# edition4-mainpart-2.net
KiCad netlist of a schematic drawn in EAGLE
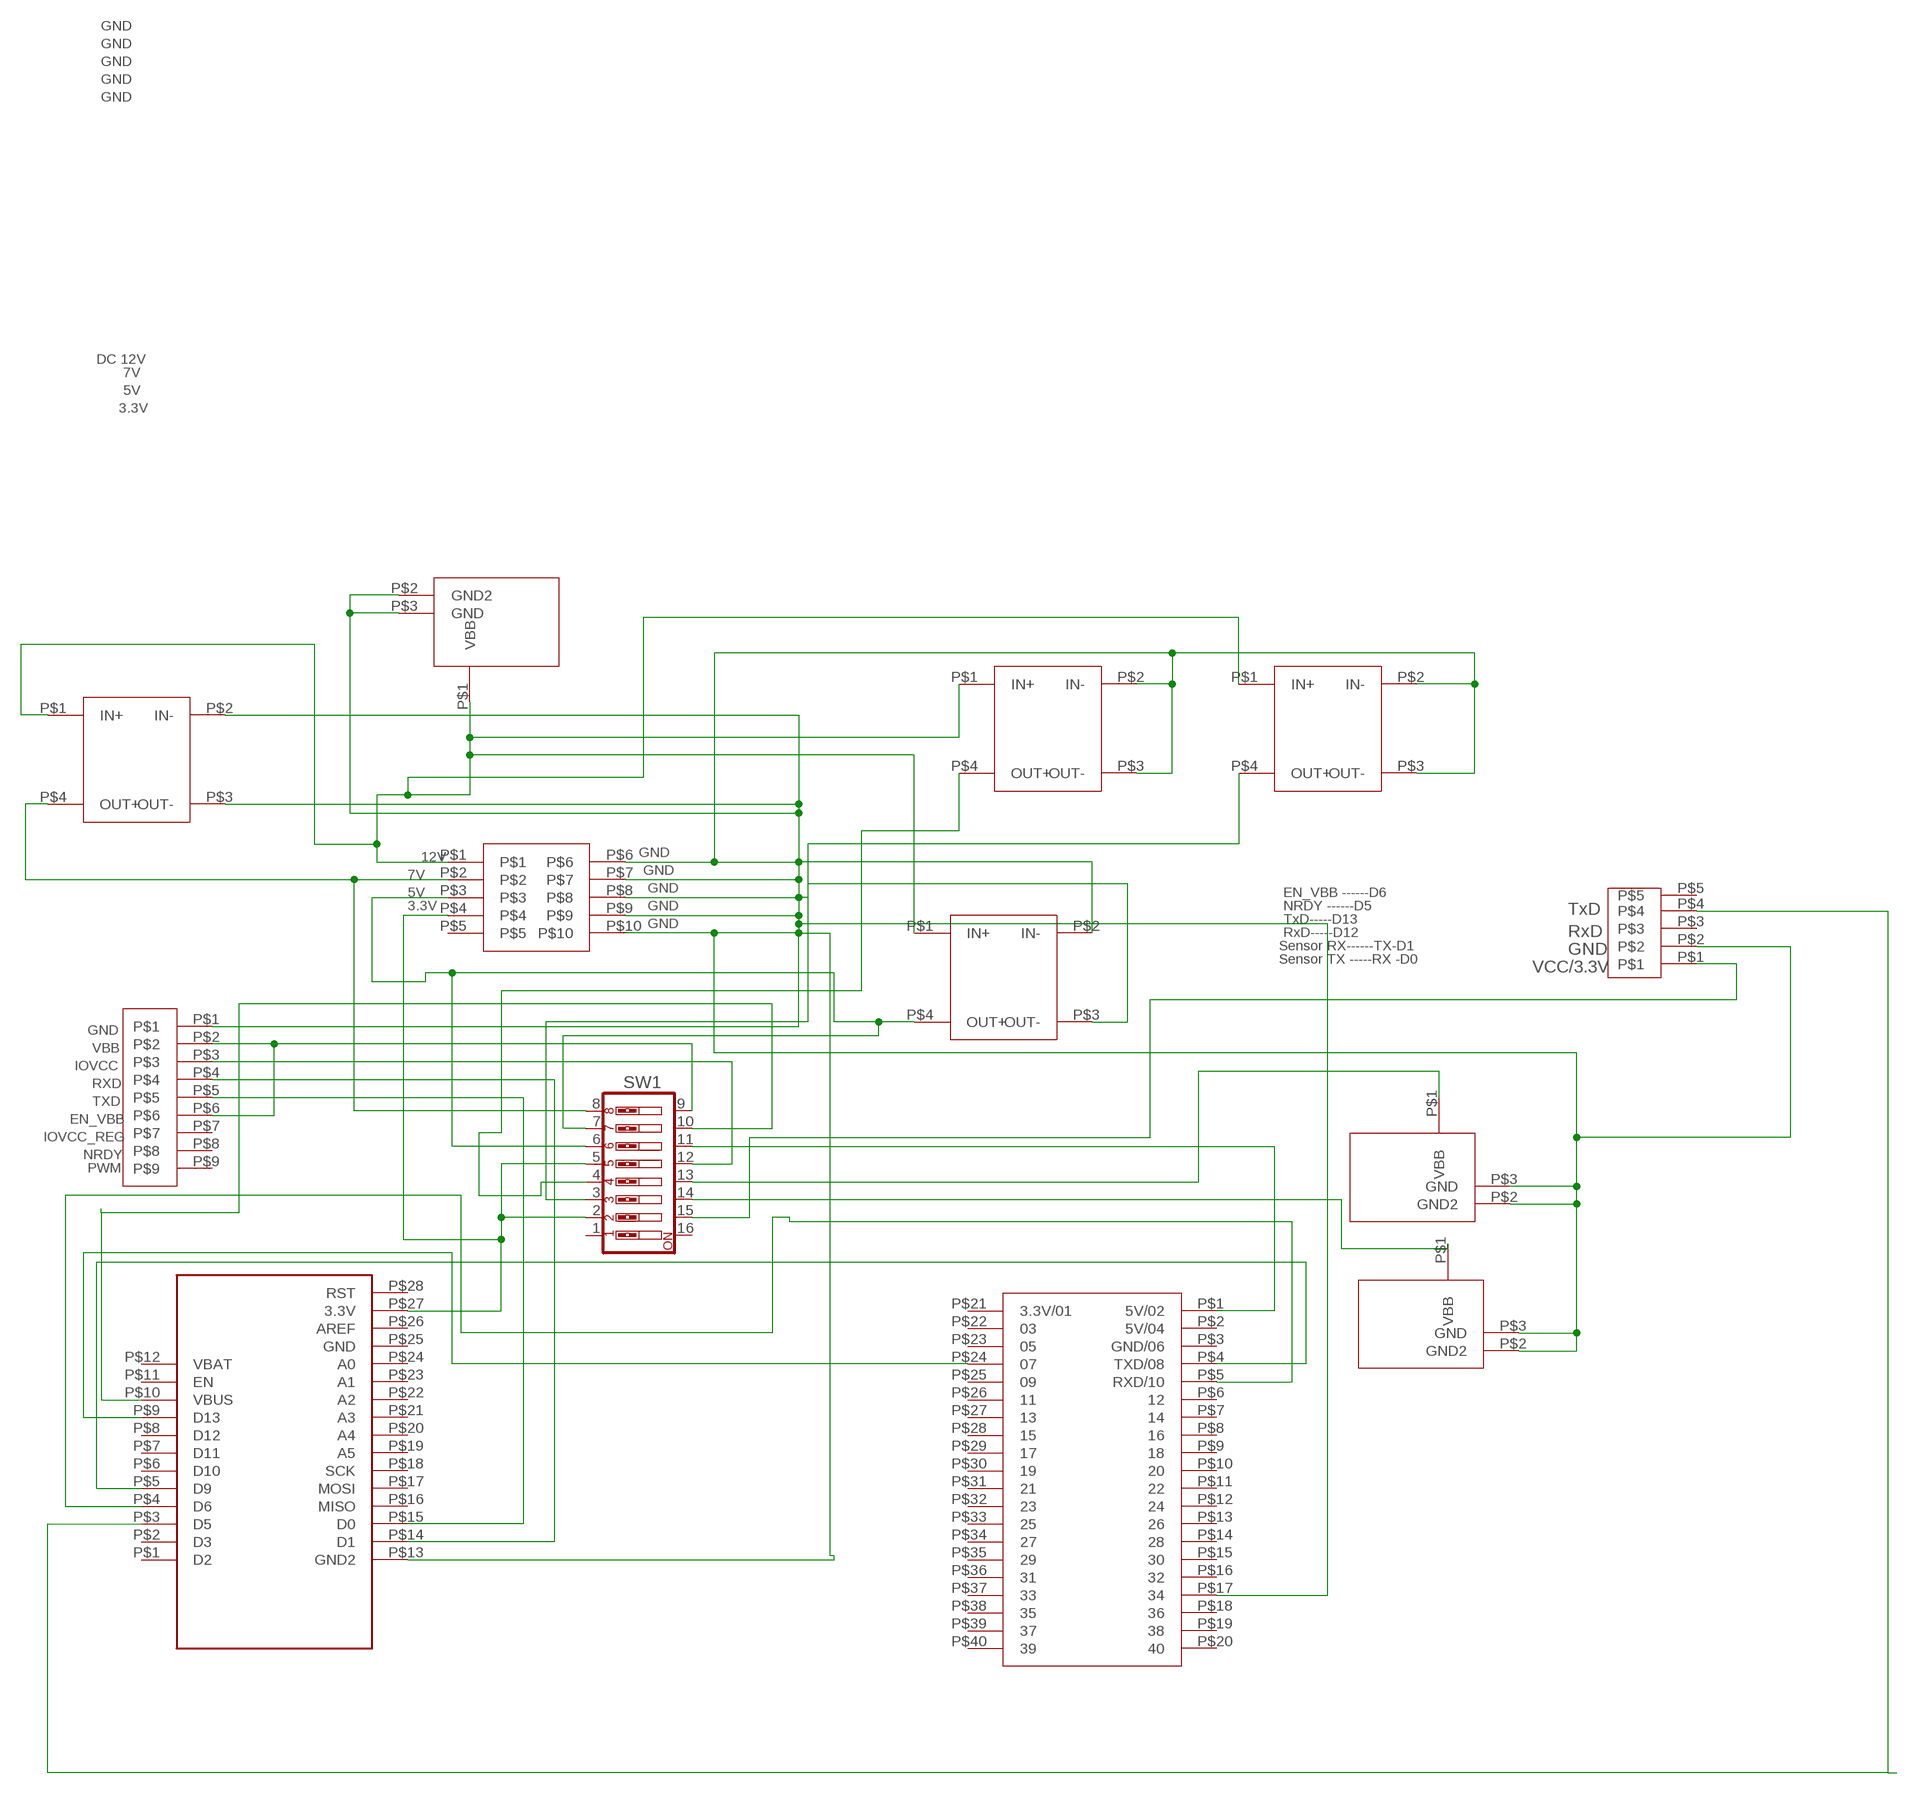
[diagram p0: schematic, sheet 1]

(export (version "E")
  (design (tool "Eeschema 10.0.6"))
  (components
    (comp (ref "SW1")
      (value "SW_DIP-8")
      (footprint "eagle-import:EDG-08")
      (libsource (lib "eagle-import") (part "SW_DIP-8"))
    )
    (comp (ref "U$1")
      (value "MH-MINI-360")
      (footprint "eagle-import:MH-MINI-360")
      (libsource (lib "eagle-import") (part "MH-MINI-360"))
    )
    (comp (ref "U$2")
      (value "MH-MINI-360")
      (footprint "eagle-import:MH-MINI-360")
      (libsource (lib "eagle-import") (part "MH-MINI-360"))
    )
    (comp (ref "U$3")
      (value "POWER")
      (footprint "eagle-import:POWERIN")
      (libsource (lib "eagle-import") (part "POWER"))
    )
    (comp (ref "U$4")
      (value "POWER")
      (footprint "eagle-import:POWERIN")
      (libsource (lib "eagle-import") (part "POWER"))
    )
    (comp (ref "U$5")
      (value "POWER")
      (footprint "eagle-import:POWERIN")
      (libsource (lib "eagle-import") (part "POWER"))
    )
    (comp (ref "U$6")
      (value "MH-MINI-360")
      (footprint "eagle-import:MH-MINI-360")
      (libsource (lib "eagle-import") (part "MH-MINI-360"))
    )
    (comp (ref "U$7")
      (value "MH-MINI-360")
      (footprint "eagle-import:MH-MINI-360")
      (libsource (lib "eagle-import") (part "MH-MINI-360"))
    )
    (comp (ref "U$8")
      (value "PIN")
      (footprint "eagle-import:PIN")
      (libsource (lib "eagle-import") (part "PIN"))
    )
    (comp (ref "U$10")
      (value "FEATHER")
      (footprint "eagle-import:FEATHER")
      (libsource (lib "eagle-import") (part "FEATHER"))
    )
    (comp (ref "U$11")
      (value "RASPBERRYPI")
      (footprint "eagle-import:RASPBERRYPI")
      (libsource (lib "eagle-import") (part "RASPBERRYPI"))
    )
    (comp (ref "U$14")
      (value "2X5FEET")
      (footprint "eagle-import:2X5FEET")
      (libsource (lib "eagle-import") (part "2X5FEET"))
    )
    (comp (ref "U$15")
      (value "9FEETPIN")
      (footprint "eagle-import:9FEETPIN")
      (libsource (lib "eagle-import") (part "9FEETPIN"))
    )
  )
  (nets
    (net (code "1") (name "Net-(SW1-Pad9)") (class "Default")
      (node (ref "SW1") (pin "9") (pinfunction "9_9") (pintype "passive"))
      (node (ref "U$15") (pin "P$2") (pinfunction "P$2_P$2") (pintype "bidirectional"))
      (node (ref "U$15") (pin "P$6") (pinfunction "P$6_P$6") (pintype "bidirectional"))
    )
    (net (code "2") (name "Net-(SW1-Pad12)") (class "Default")
      (node (ref "SW1") (pin "12") (pinfunction "12_12") (pintype "passive"))
      (node (ref "U$15") (pin "P$3") (pinfunction "P$3_P$3") (pintype "bidirectional"))
    )
    (net (code "3") (name "Net-(SW1-Pad15)") (class "Default")
      (node (ref "SW1") (pin "15") (pinfunction "15_15") (pintype "passive"))
      (node (ref "U$8") (pin "P$1") (pinfunction "P$1_P$1") (pintype "bidirectional"))
    )
    (net (code "4") (name "Net-(U$1-IN+)") (class "Default")
      (node (ref "U$1") (pin "P$1") (pinfunction "IN+_P$1") (pintype "bidirectional"))
      (node (ref "U$14") (pin "P$1") (pinfunction "P$1_P$1") (pintype "bidirectional"))
      (node (ref "U$2") (pin "P$1") (pinfunction "IN+_P$1") (pintype "bidirectional"))
      (node (ref "U$3") (pin "P$1") (pinfunction "VBB_P$1") (pintype "bidirectional"))
      (node (ref "U$6") (pin "P$1") (pinfunction "IN+_P$1") (pintype "bidirectional"))
      (node (ref "U$7") (pin "P$1") (pinfunction "IN+_P$1") (pintype "bidirectional"))
    )
    (net (code "5") (name "Net-(U$1-IN-)") (class "Default")
      (node (ref "U$1") (pin "P$2") (pinfunction "IN-_P$2") (pintype "bidirectional"))
      (node (ref "U$1") (pin "P$3") (pinfunction "OUT-_P$3") (pintype "bidirectional"))
      (node (ref "U$10") (pin "P$13") (pinfunction "GND2_P$13") (pintype "bidirectional"))
      (node (ref "U$11") (pin "P$17") (pinfunction "34_P$17") (pintype "bidirectional"))
      (node (ref "U$14") (pin "P$10") (pinfunction "P$10_P$10") (pintype "bidirectional"))
      (node (ref "U$14") (pin "P$6") (pinfunction "P$6_P$6") (pintype "bidirectional"))
      (node (ref "U$14") (pin "P$7") (pinfunction "P$7_P$7") (pintype "bidirectional"))
      (node (ref "U$14") (pin "P$8") (pinfunction "P$8_P$8") (pintype "bidirectional"))
      (node (ref "U$14") (pin "P$9") (pinfunction "P$9_P$9") (pintype "bidirectional"))
      (node (ref "U$15") (pin "P$1") (pinfunction "P$1_P$1") (pintype "bidirectional"))
      (node (ref "U$2") (pin "P$2") (pinfunction "IN-_P$2") (pintype "bidirectional"))
      (node (ref "U$2") (pin "P$3") (pinfunction "OUT-_P$3") (pintype "bidirectional"))
      (node (ref "U$3") (pin "P$2") (pinfunction "GND2_P$2") (pintype "bidirectional"))
      (node (ref "U$3") (pin "P$3") (pinfunction "GND_P$3") (pintype "bidirectional"))
      (node (ref "U$4") (pin "P$2") (pinfunction "GND2_P$2") (pintype "bidirectional"))
      (node (ref "U$4") (pin "P$3") (pinfunction "GND_P$3") (pintype "bidirectional"))
      (node (ref "U$5") (pin "P$2") (pinfunction "GND2_P$2") (pintype "bidirectional"))
      (node (ref "U$5") (pin "P$3") (pinfunction "GND_P$3") (pintype "bidirectional"))
      (node (ref "U$6") (pin "P$2") (pinfunction "IN-_P$2") (pintype "bidirectional"))
      (node (ref "U$6") (pin "P$3") (pinfunction "OUT-_P$3") (pintype "bidirectional"))
      (node (ref "U$7") (pin "P$2") (pinfunction "IN-_P$2") (pintype "bidirectional"))
      (node (ref "U$7") (pin "P$3") (pinfunction "OUT-_P$3") (pintype "bidirectional"))
      (node (ref "U$8") (pin "P$2") (pinfunction "P$2_P$2") (pintype "bidirectional"))
    )
    (net (code "6") (name "Net-(U$1-OUT+)") (class "Default")
      (node (ref "SW1") (pin "4") (pinfunction "4_4") (pintype "passive"))
      (node (ref "U$1") (pin "P$4") (pinfunction "OUT+_P$4") (pintype "bidirectional"))
    )
    (net (code "7") (name "Net-(U$2-OUT+)") (class "Default")
      (node (ref "SW1") (pin "6") (pinfunction "6_6") (pintype "passive"))
      (node (ref "SW1") (pin "7") (pinfunction "7_7") (pintype "passive"))
      (node (ref "U$14") (pin "P$3") (pinfunction "P$3_P$3") (pintype "bidirectional"))
      (node (ref "U$2") (pin "P$4") (pinfunction "OUT+_P$4") (pintype "bidirectional"))
    )
    (net (code "8") (name "Net-(U$4-VBB)") (class "Default")
      (node (ref "SW1") (pin "14") (pinfunction "14_14") (pintype "passive"))
      (node (ref "U$4") (pin "P$1") (pinfunction "VBB_P$1") (pintype "bidirectional"))
    )
    (net (code "9") (name "Net-(U$5-VBB)") (class "Default")
      (node (ref "SW1") (pin "13") (pinfunction "13_13") (pintype "passive"))
      (node (ref "U$5") (pin "P$1") (pinfunction "VBB_P$1") (pintype "bidirectional"))
    )
    (net (code "10") (name "Net-(U$6-OUT+)") (class "Default")
      (node (ref "SW1") (pin "8") (pinfunction "8_8") (pintype "passive"))
      (node (ref "U$14") (pin "P$2") (pinfunction "P$2_P$2") (pintype "bidirectional"))
      (node (ref "U$6") (pin "P$4") (pinfunction "OUT+_P$4") (pintype "bidirectional"))
    )
    (net (code "11") (name "Net-(U$7-OUT+)") (class "Default")
      (node (ref "SW1") (pin "3") (pinfunction "3_3") (pintype "passive"))
      (node (ref "U$7") (pin "P$4") (pinfunction "OUT+_P$4") (pintype "bidirectional"))
    )
    (net (code "12") (name "Net-(U$10-3.3V)") (class "Default")
      (node (ref "SW1") (pin "2") (pinfunction "2_2") (pintype "passive"))
      (node (ref "SW1") (pin "5") (pinfunction "5_5") (pintype "passive"))
      (node (ref "U$10") (pin "P$27") (pinfunction "3.3V_P$27") (pintype "bidirectional"))
      (node (ref "U$14") (pin "P$4") (pinfunction "P$4_P$4") (pintype "bidirectional"))
    )
    (net (code "13") (name "Net-(U$10-D0)") (class "Default")
      (node (ref "U$10") (pin "P$15") (pinfunction "D0_P$15") (pintype "bidirectional"))
      (node (ref "U$15") (pin "P$5") (pinfunction "P$5_P$5") (pintype "bidirectional"))
    )
    (net (code "14") (name "Net-(U$10-D1)") (class "Default")
      (node (ref "U$10") (pin "P$14") (pinfunction "D1_P$14") (pintype "bidirectional"))
      (node (ref "U$15") (pin "P$4") (pinfunction "P$4_P$4") (pintype "bidirectional"))
    )
    (net (code "15") (name "Net-(U$10-D5)") (class "Default")
      (node (ref "U$10") (pin "P$3") (pinfunction "D5_P$3") (pintype "bidirectional"))
      (node (ref "U$8") (pin "P$4") (pinfunction "P$4_P$4") (pintype "bidirectional"))
    )
    (net (code "16") (name "Net-(U$10-D6)") (class "Default")
      (node (ref "U$10") (pin "P$4") (pinfunction "D6_P$4") (pintype "bidirectional"))
      (node (ref "U$11") (pin "P$5") (pinfunction "RXD/10_P$5") (pintype "bidirectional"))
    )
    (net (code "17") (name "Net-(U$10-D9)") (class "Default")
      (node (ref "U$10") (pin "P$5") (pinfunction "D9_P$5") (pintype "bidirectional"))
      (node (ref "U$11") (pin "P$4") (pinfunction "TXD/08_P$4") (pintype "bidirectional"))
    )
    (net (code "18") (name "Net-(U$10-D13)") (class "Default")
      (node (ref "U$10") (pin "P$9") (pinfunction "D13_P$9") (pintype "bidirectional"))
      (node (ref "U$11") (pin "P$24") (pinfunction "07_P$24") (pintype "bidirectional"))
    )
    (net (code "19") (name "Net-(U$10-VBUS)") (class "Default")
      (node (ref "SW1") (pin "10") (pinfunction "10_10") (pintype "passive"))
      (node (ref "U$10") (pin "P$10") (pinfunction "VBUS_P$10") (pintype "bidirectional"))
    )
    (net (code "20") (name "Net-(U$11-5V{slash}02)") (class "Default")
      (node (ref "SW1") (pin "11") (pinfunction "11_11") (pintype "passive"))
      (node (ref "U$11") (pin "P$1") (pinfunction "5V/02_P$1") (pintype "bidirectional"))
    )
    (net (code "21") (name "unconnected-(SW1-Pad1)") (class "Default")
      (node (ref "SW1") (pin "1") (pinfunction "1_1") (pintype "passive"))
    )
    (net (code "22") (name "unconnected-(SW1-Pad16)") (class "Default")
      (node (ref "SW1") (pin "16") (pinfunction "16_16") (pintype "passive"))
    )
    (net (code "23") (name "unconnected-(U$8-PadP$3)") (class "Default")
      (node (ref "U$8") (pin "P$3") (pinfunction "P$3_P$3") (pintype "bidirectional"))
    )
    (net (code "24") (name "unconnected-(U$8-PadP$5)") (class "Default")
      (node (ref "U$8") (pin "P$5") (pinfunction "P$5_P$5") (pintype "bidirectional"))
    )
    (net (code "25") (name "unconnected-(U$10-A0-PadP$24)") (class "Default")
      (node (ref "U$10") (pin "P$24") (pinfunction "A0_P$24") (pintype "bidirectional"))
    )
    (net (code "26") (name "unconnected-(U$10-A1-PadP$23)") (class "Default")
      (node (ref "U$10") (pin "P$23") (pinfunction "A1_P$23") (pintype "bidirectional"))
    )
    (net (code "27") (name "unconnected-(U$10-A2-PadP$22)") (class "Default")
      (node (ref "U$10") (pin "P$22") (pinfunction "A2_P$22") (pintype "bidirectional"))
    )
    (net (code "28") (name "unconnected-(U$10-A3-PadP$21)") (class "Default")
      (node (ref "U$10") (pin "P$21") (pinfunction "A3_P$21") (pintype "bidirectional"))
    )
    (net (code "29") (name "unconnected-(U$10-A4-PadP$20)") (class "Default")
      (node (ref "U$10") (pin "P$20") (pinfunction "A4_P$20") (pintype "bidirectional"))
    )
    (net (code "30") (name "unconnected-(U$10-A5-PadP$19)") (class "Default")
      (node (ref "U$10") (pin "P$19") (pinfunction "A5_P$19") (pintype "bidirectional"))
    )
    (net (code "31") (name "unconnected-(U$10-AREF-PadP$26)") (class "Default")
      (node (ref "U$10") (pin "P$26") (pinfunction "AREF_P$26") (pintype "bidirectional"))
    )
    (net (code "32") (name "unconnected-(U$10-D2-PadP$1)") (class "Default")
      (node (ref "U$10") (pin "P$1") (pinfunction "D2_P$1") (pintype "bidirectional"))
    )
    (net (code "33") (name "unconnected-(U$10-D3-PadP$2)") (class "Default")
      (node (ref "U$10") (pin "P$2") (pinfunction "D3_P$2") (pintype "bidirectional"))
    )
    (net (code "34") (name "unconnected-(U$10-D10-PadP$6)") (class "Default")
      (node (ref "U$10") (pin "P$6") (pinfunction "D10_P$6") (pintype "bidirectional"))
    )
    (net (code "35") (name "unconnected-(U$10-D11-PadP$7)") (class "Default")
      (node (ref "U$10") (pin "P$7") (pinfunction "D11_P$7") (pintype "bidirectional"))
    )
    (net (code "36") (name "unconnected-(U$10-D12-PadP$8)") (class "Default")
      (node (ref "U$10") (pin "P$8") (pinfunction "D12_P$8") (pintype "bidirectional"))
    )
    (net (code "37") (name "unconnected-(U$10-EN-PadP$11)") (class "Default")
      (node (ref "U$10") (pin "P$11") (pinfunction "EN_P$11") (pintype "bidirectional"))
    )
    (net (code "38") (name "unconnected-(U$10-GND-PadP$25)") (class "Default")
      (node (ref "U$10") (pin "P$25") (pinfunction "GND_P$25") (pintype "bidirectional"))
    )
    (net (code "39") (name "unconnected-(U$10-MISO-PadP$16)") (class "Default")
      (node (ref "U$10") (pin "P$16") (pinfunction "MISO_P$16") (pintype "bidirectional"))
    )
    (net (code "40") (name "unconnected-(U$10-MOSI-PadP$17)") (class "Default")
      (node (ref "U$10") (pin "P$17") (pinfunction "MOSI_P$17") (pintype "bidirectional"))
    )
    (net (code "41") (name "unconnected-(U$10-RST-PadP$28)") (class "Default")
      (node (ref "U$10") (pin "P$28") (pinfunction "RST_P$28") (pintype "bidirectional"))
    )
    (net (code "42") (name "unconnected-(U$10-SCK-PadP$18)") (class "Default")
      (node (ref "U$10") (pin "P$18") (pinfunction "SCK_P$18") (pintype "bidirectional"))
    )
    (net (code "43") (name "unconnected-(U$10-VBAT-PadP$12)") (class "Default")
      (node (ref "U$10") (pin "P$12") (pinfunction "VBAT_P$12") (pintype "bidirectional"))
    )
    (net (code "44") (name "unconnected-(U$11-03-PadP$22)") (class "Default")
      (node (ref "U$11") (pin "P$22") (pinfunction "03_P$22") (pintype "bidirectional"))
    )
    (net (code "45") (name "unconnected-(U$11-3.3V{slash}01-PadP$21)") (class "Default")
      (node (ref "U$11") (pin "P$21") (pinfunction "3.3V/01_P$21") (pintype "bidirectional"))
    )
    (net (code "46") (name "unconnected-(U$11-05-PadP$23)") (class "Default")
      (node (ref "U$11") (pin "P$23") (pinfunction "05_P$23") (pintype "bidirectional"))
    )
    (net (code "47") (name "unconnected-(U$11-5V{slash}04-PadP$2)") (class "Default")
      (node (ref "U$11") (pin "P$2") (pinfunction "5V/04_P$2") (pintype "bidirectional"))
    )
    (net (code "48") (name "unconnected-(U$11-09-PadP$25)") (class "Default")
      (node (ref "U$11") (pin "P$25") (pinfunction "09_P$25") (pintype "bidirectional"))
    )
    (net (code "49") (name "unconnected-(U$11-11-PadP$26)") (class "Default")
      (node (ref "U$11") (pin "P$26") (pinfunction "11_P$26") (pintype "bidirectional"))
    )
    (net (code "50") (name "unconnected-(U$11-12-PadP$6)") (class "Default")
      (node (ref "U$11") (pin "P$6") (pinfunction "12_P$6") (pintype "bidirectional"))
    )
    (net (code "51") (name "unconnected-(U$11-13-PadP$27)") (class "Default")
      (node (ref "U$11") (pin "P$27") (pinfunction "13_P$27") (pintype "bidirectional"))
    )
    (net (code "52") (name "unconnected-(U$11-14-PadP$7)") (class "Default")
      (node (ref "U$11") (pin "P$7") (pinfunction "14_P$7") (pintype "bidirectional"))
    )
    (net (code "53") (name "unconnected-(U$11-15-PadP$28)") (class "Default")
      (node (ref "U$11") (pin "P$28") (pinfunction "15_P$28") (pintype "bidirectional"))
    )
    (net (code "54") (name "unconnected-(U$11-16-PadP$8)") (class "Default")
      (node (ref "U$11") (pin "P$8") (pinfunction "16_P$8") (pintype "bidirectional"))
    )
    (net (code "55") (name "unconnected-(U$11-17-PadP$29)") (class "Default")
      (node (ref "U$11") (pin "P$29") (pinfunction "17_P$29") (pintype "bidirectional"))
    )
    (net (code "56") (name "unconnected-(U$11-18-PadP$9)") (class "Default")
      (node (ref "U$11") (pin "P$9") (pinfunction "18_P$9") (pintype "bidirectional"))
    )
    (net (code "57") (name "unconnected-(U$11-19-PadP$30)") (class "Default")
      (node (ref "U$11") (pin "P$30") (pinfunction "19_P$30") (pintype "bidirectional"))
    )
    (net (code "58") (name "unconnected-(U$11-20-PadP$10)") (class "Default")
      (node (ref "U$11") (pin "P$10") (pinfunction "20_P$10") (pintype "bidirectional"))
    )
    (net (code "59") (name "unconnected-(U$11-21-PadP$31)") (class "Default")
      (node (ref "U$11") (pin "P$31") (pinfunction "21_P$31") (pintype "bidirectional"))
    )
    (net (code "60") (name "unconnected-(U$11-22-PadP$11)") (class "Default")
      (node (ref "U$11") (pin "P$11") (pinfunction "22_P$11") (pintype "bidirectional"))
    )
    (net (code "61") (name "unconnected-(U$11-23-PadP$32)") (class "Default")
      (node (ref "U$11") (pin "P$32") (pinfunction "23_P$32") (pintype "bidirectional"))
    )
    (net (code "62") (name "unconnected-(U$11-24-PadP$12)") (class "Default")
      (node (ref "U$11") (pin "P$12") (pinfunction "24_P$12") (pintype "bidirectional"))
    )
    (net (code "63") (name "unconnected-(U$11-25-PadP$33)") (class "Default")
      (node (ref "U$11") (pin "P$33") (pinfunction "25_P$33") (pintype "bidirectional"))
    )
    (net (code "64") (name "unconnected-(U$11-26-PadP$13)") (class "Default")
      (node (ref "U$11") (pin "P$13") (pinfunction "26_P$13") (pintype "bidirectional"))
    )
    (net (code "65") (name "unconnected-(U$11-27-PadP$34)") (class "Default")
      (node (ref "U$11") (pin "P$34") (pinfunction "27_P$34") (pintype "bidirectional"))
    )
    (net (code "66") (name "unconnected-(U$11-28-PadP$14)") (class "Default")
      (node (ref "U$11") (pin "P$14") (pinfunction "28_P$14") (pintype "bidirectional"))
    )
    (net (code "67") (name "unconnected-(U$11-29-PadP$35)") (class "Default")
      (node (ref "U$11") (pin "P$35") (pinfunction "29_P$35") (pintype "bidirectional"))
    )
    (net (code "68") (name "unconnected-(U$11-30-PadP$15)") (class "Default")
      (node (ref "U$11") (pin "P$15") (pinfunction "30_P$15") (pintype "bidirectional"))
    )
    (net (code "69") (name "unconnected-(U$11-31-PadP$36)") (class "Default")
      (node (ref "U$11") (pin "P$36") (pinfunction "31_P$36") (pintype "bidirectional"))
    )
    (net (code "70") (name "unconnected-(U$11-32-PadP$16)") (class "Default")
      (node (ref "U$11") (pin "P$16") (pinfunction "32_P$16") (pintype "bidirectional"))
    )
    (net (code "71") (name "unconnected-(U$11-33-PadP$37)") (class "Default")
      (node (ref "U$11") (pin "P$37") (pinfunction "33_P$37") (pintype "bidirectional"))
    )
    (net (code "72") (name "unconnected-(U$11-35-PadP$38)") (class "Default")
      (node (ref "U$11") (pin "P$38") (pinfunction "35_P$38") (pintype "bidirectional"))
    )
    (net (code "73") (name "unconnected-(U$11-36-PadP$18)") (class "Default")
      (node (ref "U$11") (pin "P$18") (pinfunction "36_P$18") (pintype "bidirectional"))
    )
    (net (code "74") (name "unconnected-(U$11-37-PadP$39)") (class "Default")
      (node (ref "U$11") (pin "P$39") (pinfunction "37_P$39") (pintype "bidirectional"))
    )
    (net (code "75") (name "unconnected-(U$11-38-PadP$19)") (class "Default")
      (node (ref "U$11") (pin "P$19") (pinfunction "38_P$19") (pintype "bidirectional"))
    )
    (net (code "76") (name "unconnected-(U$11-39-PadP$40)") (class "Default")
      (node (ref "U$11") (pin "P$40") (pinfunction "39_P$40") (pintype "bidirectional"))
    )
    (net (code "77") (name "unconnected-(U$11-40-PadP$20)") (class "Default")
      (node (ref "U$11") (pin "P$20") (pinfunction "40_P$20") (pintype "bidirectional"))
    )
    (net (code "78") (name "unconnected-(U$11-GND{slash}06-PadP$3)") (class "Default")
      (node (ref "U$11") (pin "P$3") (pinfunction "GND/06_P$3") (pintype "bidirectional"))
    )
    (net (code "79") (name "unconnected-(U$14-PadP$5)") (class "Default")
      (node (ref "U$14") (pin "P$5") (pinfunction "P$5_P$5") (pintype "bidirectional"))
    )
    (net (code "80") (name "unconnected-(U$15-PadP$7)") (class "Default")
      (node (ref "U$15") (pin "P$7") (pinfunction "P$7_P$7") (pintype "bidirectional"))
    )
    (net (code "81") (name "unconnected-(U$15-PadP$8)") (class "Default")
      (node (ref "U$15") (pin "P$8") (pinfunction "P$8_P$8") (pintype "bidirectional"))
    )
    (net (code "82") (name "unconnected-(U$15-PadP$9)") (class "Default")
      (node (ref "U$15") (pin "P$9") (pinfunction "P$9_P$9") (pintype "bidirectional"))
    )
  )
)
